# SAVMakerI.net
KiCad netlist of a schematic drawn in EAGLE
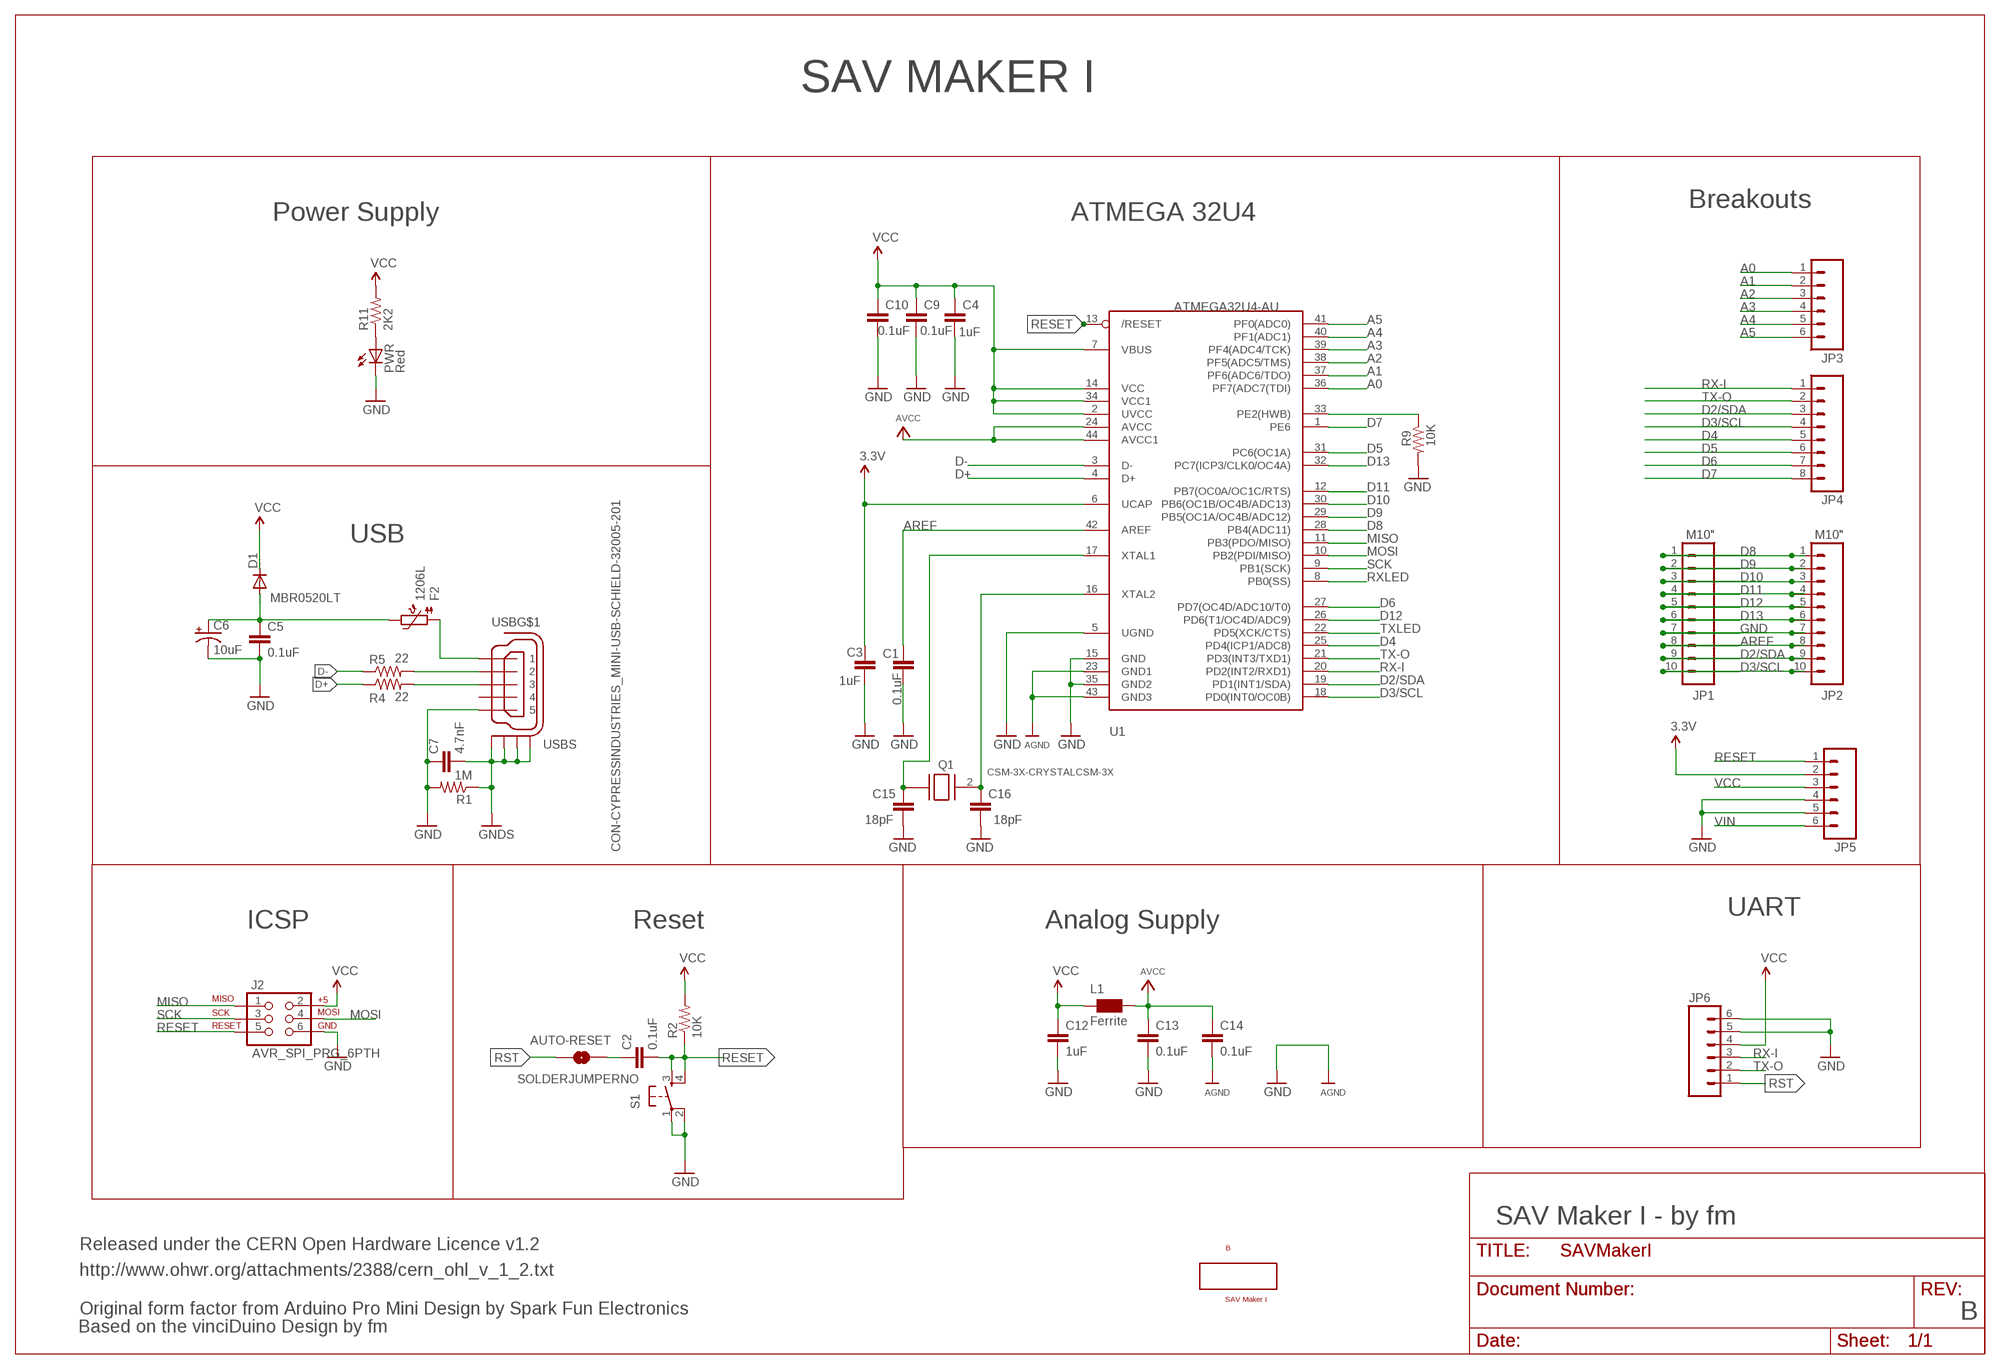
[diagram p0: schematic, sheet 1]

(export (version "E")
  (design (tool "Eeschema 10.0.6"))
  (components
    (comp (ref "AUTO-RESET")
      (value "SOLDERJUMPERNO")
      (footprint "eagle-import:SJ_2S-NO")
      (libsource (lib "eagle-import") (part "SOLDERJUMPERNO"))
    )
    (comp (ref "B")
      (value "SAV Maker I")
      (footprint "eagle-import:BOARD_INFO_BMP")
      (libsource (lib "eagle-import") (part "BOARD_INFO_BMP_20"))
    )
    (comp (ref "C1")
      (value "0.1uF")
      (footprint "eagle-import:1206")
      (libsource (lib "eagle-import") (part "CAP1206"))
    )
    (comp (ref "C2")
      (value "0.1uF")
      (footprint "eagle-import:1206")
      (libsource (lib "eagle-import") (part "CAP1206"))
    )
    (comp (ref "C3")
      (value "1uF")
      (footprint "eagle-import:1206")
      (libsource (lib "eagle-import") (part "CAP1206"))
    )
    (comp (ref "C4")
      (value "1uF")
      (footprint "eagle-import:1206")
      (libsource (lib "eagle-import") (part "CAP1206"))
    )
    (comp (ref "C5")
      (value "0.1uF")
      (footprint "eagle-import:1206")
      (libsource (lib "eagle-import") (part "CAP1206"))
    )
    (comp (ref "C6")
      (value "10uF")
      (footprint "eagle-import:EIA3216")
      (libsource (lib "eagle-import") (part "CAP_POL1206"))
    )
    (comp (ref "C7")
      (value "4.7nF")
      (footprint "eagle-import:1206")
      (libsource (lib "eagle-import") (part "CAP1206"))
    )
    (comp (ref "C9")
      (value "0.1uF")
      (footprint "eagle-import:1206")
      (libsource (lib "eagle-import") (part "CAP1206"))
    )
    (comp (ref "C10")
      (value "0.1uF")
      (footprint "eagle-import:1206")
      (libsource (lib "eagle-import") (part "CAP1206"))
    )
    (comp (ref "C12")
      (value "1uF")
      (footprint "eagle-import:1206")
      (libsource (lib "eagle-import") (part "CAP1206"))
    )
    (comp (ref "C13")
      (value "0.1uF")
      (footprint "eagle-import:1206")
      (libsource (lib "eagle-import") (part "CAP1206"))
    )
    (comp (ref "C14")
      (value "0.1uF")
      (footprint "eagle-import:1206")
      (libsource (lib "eagle-import") (part "CAP1206"))
    )
    (comp (ref "C15")
      (value "18pF")
      (footprint "eagle-import:1206")
      (libsource (lib "eagle-import") (part "CAP1206"))
    )
    (comp (ref "C16")
      (value "18pF")
      (footprint "eagle-import:1206")
      (libsource (lib "eagle-import") (part "CAP1206"))
    )
    (comp (ref "D1")
      (value "MBR0520LT")
      (footprint "eagle-import:SOD123")
      (libsource (lib "eagle-import") (part "MBR0520LT"))
    )
    (comp (ref "F2")
      (value "1206L")
      (footprint "eagle-import:1206_PTC")
      (libsource (lib "eagle-import") (part "PTC1206_L"))
    )
    (comp (ref "J2")
      (value "AVR_SPI_PRG_6PTH")
      (footprint "eagle-import:2X3")
      (libsource (lib "eagle-import") (part "AVR_SPI_PRG_6PTH"))
    )
    (comp (ref "JP1")
      (value "M10\"")
      (footprint "eagle-import:1X10")
      (libsource (lib "eagle-import") (part "M10{dblquote}"))
    )
    (comp (ref "JP2")
      (value "M10\"")
      (footprint "eagle-import:1X10")
      (libsource (lib "eagle-import") (part "M10{dblquote}"))
    )
    (comp (ref "JP3")
      (value "M06SIP")
      (footprint "eagle-import:1X06")
      (libsource (lib "eagle-import") (part "M06SIP"))
    )
    (comp (ref "JP4")
      (value "M081X08")
      (footprint "eagle-import:1X08")
      (libsource (lib "eagle-import") (part "M081X08"))
    )
    (comp (ref "JP5")
      (value "M06SIP")
      (footprint "eagle-import:1X06")
      (libsource (lib "eagle-import") (part "M06SIP"))
    )
    (comp (ref "JP6")
      (value "M06SIP")
      (footprint "eagle-import:1X06")
      (libsource (lib "eagle-import") (part "M06SIP"))
    )
    (comp (ref "L1")
      (value "Ferrite")
      (footprint "eagle-import:1206W")
      (libsource (lib "eagle-import") (part "WE-CBF_1206W"))
    )
    (comp (ref "PWR")
      (value "Red")
      (footprint "eagle-import:LED-1206")
      (libsource (lib "eagle-import") (part "LED1206"))
    )
    (comp (ref "Q1")
      (value "CSM-3X-CRYSTALCSM-3X")
      (footprint "eagle-import:CSM-3X")
      (libsource (lib "eagle-import") (part "CSM-3X-CRYSTALCSM-3X"))
    )
    (comp (ref "R1")
      (value "1M")
      (footprint "eagle-import:R1206")
      (libsource (lib "eagle-import") (part "R-US_R1206"))
    )
    (comp (ref "R2")
      (value "10K")
      (footprint "eagle-import:R1206")
      (libsource (lib "eagle-import") (part "R-US_R1206"))
    )
    (comp (ref "R4")
      (value "22")
      (footprint "eagle-import:R1206")
      (libsource (lib "eagle-import") (part "R-US_R1206"))
    )
    (comp (ref "R5")
      (value "22")
      (footprint "eagle-import:R1206")
      (libsource (lib "eagle-import") (part "R-US_R1206"))
    )
    (comp (ref "R9")
      (value "10K")
      (footprint "eagle-import:R1206")
      (libsource (lib "eagle-import") (part "R-US_R1206"))
    )
    (comp (ref "R11")
      (value "2K2")
      (footprint "eagle-import:R1206")
      (libsource (lib "eagle-import") (part "R-US_R1206"))
    )
    (comp (ref "S1")
      (value "TAC_SWITCHSMD")
      (footprint "eagle-import:TACTILE_SWITCH_SMD")
      (libsource (lib "eagle-import") (part "TAC_SWITCHSMD"))
    )
    (comp (ref "U1")
      (value "ATMEGA32U4-AU")
      (footprint "eagle-import:ADAFRUIT_TQFP44")
      (libsource (lib "eagle-import") (part "ADAFRUIT_ATMEGA32U4-AU"))
    )
    (comp (ref "USB")
      (value "CON-CYPRESSINDUSTRIES_MINI-USB-SCHIELD-32005-201")
      (footprint "eagle-import:CON-CYPRESSINDUSTRIES_32005-201")
      (libsource (lib "eagle-import") (part "CON-CYPRESSINDUSTRIES_MINI-USB-SCHIELD-32005-201"))
    )
  )
  (nets
    (net (code "1") (name "/A0") (class "Default")
      (node (ref "JP3") (pin "1") (pinfunction "1_1") (pintype "passive"))
      (node (ref "U1") (pin "36") (pinfunction "PF7(ADC7(TDI)_36") (pintype "bidirectional"))
    )
    (net (code "2") (name "/A1") (class "Default")
      (node (ref "JP3") (pin "2") (pinfunction "2_2") (pintype "passive"))
      (node (ref "U1") (pin "37") (pinfunction "PF6(ADC6/TDO)_37") (pintype "bidirectional"))
    )
    (net (code "3") (name "/A2") (class "Default")
      (node (ref "JP3") (pin "3") (pinfunction "3_3") (pintype "passive"))
      (node (ref "U1") (pin "38") (pinfunction "PF5(ADC5/TMS)_38") (pintype "bidirectional"))
    )
    (net (code "4") (name "/A3") (class "Default")
      (node (ref "JP3") (pin "4") (pinfunction "4_4") (pintype "passive"))
      (node (ref "U1") (pin "39") (pinfunction "PF4(ADC4/TCK)_39") (pintype "bidirectional"))
    )
    (net (code "5") (name "/A4") (class "Default")
      (node (ref "JP3") (pin "5") (pinfunction "5_5") (pintype "passive"))
      (node (ref "U1") (pin "40") (pinfunction "PF1(ADC1)_40") (pintype "bidirectional"))
    )
    (net (code "6") (name "/A5") (class "Default")
      (node (ref "JP3") (pin "6") (pinfunction "6_6") (pintype "passive"))
      (node (ref "U1") (pin "41") (pinfunction "PF0(ADC0)_41") (pintype "bidirectional"))
    )
    (net (code "7") (name "/AREF") (class "Default")
      (node (ref "C1") (pin "2") (pinfunction "2_2") (pintype "passive"))
      (node (ref "JP1") (pin "8") (pinfunction "8_8") (pintype "passive"))
      (node (ref "JP2") (pin "8") (pinfunction "8_8") (pintype "passive"))
      (node (ref "U1") (pin "42") (pinfunction "AREF_42") (pintype "bidirectional"))
    )
    (net (code "8") (name "/D2{slash}SDA") (class "Default")
      (node (ref "JP1") (pin "9") (pinfunction "9_9") (pintype "passive"))
      (node (ref "JP2") (pin "9") (pinfunction "9_9") (pintype "passive"))
      (node (ref "JP4") (pin "3") (pinfunction "3_3") (pintype "passive"))
      (node (ref "U1") (pin "19") (pinfunction "PD1(INT1/SDA)_19") (pintype "bidirectional"))
    )
    (net (code "9") (name "/D3{slash}SCL") (class "Default")
      (node (ref "JP1") (pin "10") (pinfunction "10_10") (pintype "passive"))
      (node (ref "JP2") (pin "10") (pinfunction "10_10") (pintype "passive"))
      (node (ref "JP4") (pin "4") (pinfunction "4_4") (pintype "passive"))
      (node (ref "U1") (pin "18") (pinfunction "PD0(INT0/OC0B)_18") (pintype "bidirectional"))
    )
    (net (code "10") (name "/D4") (class "Default")
      (node (ref "JP4") (pin "5") (pinfunction "5_5") (pintype "passive"))
      (node (ref "U1") (pin "25") (pinfunction "PD4(ICP1/ADC8)_25") (pintype "bidirectional"))
    )
    (net (code "11") (name "/D5") (class "Default")
      (node (ref "JP4") (pin "6") (pinfunction "6_6") (pintype "passive"))
      (node (ref "U1") (pin "31") (pinfunction "PC6(OC1A)_31") (pintype "bidirectional"))
    )
    (net (code "12") (name "/D6") (class "Default")
      (node (ref "JP4") (pin "7") (pinfunction "7_7") (pintype "passive"))
      (node (ref "U1") (pin "27") (pinfunction "PD7(OC4D/ADC10/T0)_27") (pintype "bidirectional"))
    )
    (net (code "13") (name "/D7") (class "Default")
      (node (ref "JP4") (pin "8") (pinfunction "8_8") (pintype "passive"))
      (node (ref "U1") (pin "1") (pinfunction "PE6_1") (pintype "bidirectional"))
    )
    (net (code "14") (name "/D8") (class "Default")
      (node (ref "JP1") (pin "1") (pinfunction "1_1") (pintype "passive"))
      (node (ref "JP2") (pin "1") (pinfunction "1_1") (pintype "passive"))
      (node (ref "U1") (pin "28") (pinfunction "PB4(ADC11)_28") (pintype "bidirectional"))
    )
    (net (code "15") (name "/D9") (class "Default")
      (node (ref "JP1") (pin "2") (pinfunction "2_2") (pintype "passive"))
      (node (ref "JP2") (pin "2") (pinfunction "2_2") (pintype "passive"))
      (node (ref "U1") (pin "29") (pinfunction "PB5(OC1A/OC4B/ADC12)_29") (pintype "bidirectional"))
    )
    (net (code "16") (name "/D10") (class "Default")
      (node (ref "JP1") (pin "3") (pinfunction "3_3") (pintype "passive"))
      (node (ref "JP2") (pin "3") (pinfunction "3_3") (pintype "passive"))
      (node (ref "U1") (pin "30") (pinfunction "PB6(OC1B/OC4B/ADC13)_30") (pintype "bidirectional"))
    )
    (net (code "17") (name "/D11") (class "Default")
      (node (ref "JP1") (pin "4") (pinfunction "4_4") (pintype "passive"))
      (node (ref "JP2") (pin "4") (pinfunction "4_4") (pintype "passive"))
      (node (ref "U1") (pin "12") (pinfunction "PB7(OC0A/OC1C/RTS)_12") (pintype "bidirectional"))
    )
    (net (code "18") (name "/D12") (class "Default")
      (node (ref "JP1") (pin "5") (pinfunction "5_5") (pintype "passive"))
      (node (ref "JP2") (pin "5") (pinfunction "5_5") (pintype "passive"))
      (node (ref "U1") (pin "26") (pinfunction "PD6(T1/OC4D/ADC9)_26") (pintype "bidirectional"))
    )
    (net (code "19") (name "/D13") (class "Default")
      (node (ref "JP1") (pin "6") (pinfunction "6_6") (pintype "passive"))
      (node (ref "JP2") (pin "6") (pinfunction "6_6") (pintype "passive"))
      (node (ref "U1") (pin "32") (pinfunction "PC7(ICP3/CLK0/OC4A)_32") (pintype "bidirectional"))
    )
    (net (code "20") (name "/MISO") (class "Default")
      (node (ref "J2") (pin "1") (pinfunction "1_1") (pintype "passive"))
      (node (ref "U1") (pin "11") (pinfunction "PB3(PDO/MISO)_11") (pintype "bidirectional"))
    )
    (net (code "21") (name "/MOSI") (class "Default")
      (node (ref "J2") (pin "4") (pinfunction "4_4") (pintype "passive"))
      (node (ref "U1") (pin "10") (pinfunction "PB2(PDI/MISO)_10") (pintype "bidirectional"))
    )
    (net (code "22") (name "/RX-I") (class "Default")
      (node (ref "JP4") (pin "1") (pinfunction "1_1") (pintype "passive"))
      (node (ref "JP6") (pin "3") (pinfunction "3_3") (pintype "passive"))
      (node (ref "U1") (pin "20") (pinfunction "PD2(INT2/RXD1)_20") (pintype "bidirectional"))
    )
    (net (code "23") (name "/RXLED") (class "Default")
      (node (ref "U1") (pin "8") (pinfunction "PB0(SS)_8") (pintype "bidirectional"))
    )
    (net (code "24") (name "/SCK") (class "Default")
      (node (ref "J2") (pin "3") (pinfunction "3_3") (pintype "passive"))
      (node (ref "U1") (pin "9") (pinfunction "PB1(SCK)_9") (pintype "bidirectional"))
    )
    (net (code "25") (name "/TX-O") (class "Default")
      (node (ref "JP4") (pin "2") (pinfunction "2_2") (pintype "passive"))
      (node (ref "JP6") (pin "2") (pinfunction "2_2") (pintype "passive"))
      (node (ref "U1") (pin "21") (pinfunction "PD3(INT3/TXD1)_21") (pintype "bidirectional"))
    )
    (net (code "26") (name "/TXLED") (class "Default")
      (node (ref "U1") (pin "22") (pinfunction "PD5(XCK/CTS)_22") (pintype "bidirectional"))
    )
    (net (code "27") (name "/VIN") (class "Default")
      (node (ref "JP5") (pin "6") (pinfunction "6_6") (pintype "passive"))
    )
    (net (code "28") (name "3.3V") (class "Default")
      (node (ref "C3") (pin "1") (pinfunction "1_1") (pintype "passive"))
      (node (ref "JP5") (pin "2") (pinfunction "2_2") (pintype "passive"))
      (node (ref "U1") (pin "6") (pinfunction "UCAP_6") (pintype "bidirectional"))
    )
    (net (code "29") (name "AGND") (class "Default")
      (node (ref "C1") (pin "1") (pinfunction "1_1") (pintype "passive"))
      (node (ref "C10") (pin "2") (pinfunction "2_2") (pintype "passive"))
      (node (ref "C12") (pin "2") (pinfunction "2_2") (pintype "passive"))
      (node (ref "C13") (pin "2") (pinfunction "2_2") (pintype "passive"))
      (node (ref "C14") (pin "2") (pinfunction "2_2") (pintype "passive"))
      (node (ref "C15") (pin "2") (pinfunction "2_2") (pintype "passive"))
      (node (ref "C16") (pin "2") (pinfunction "2_2") (pintype "passive"))
      (node (ref "C3") (pin "2") (pinfunction "2_2") (pintype "passive"))
      (node (ref "C4") (pin "2") (pinfunction "2_2") (pintype "passive"))
      (node (ref "C5") (pin "2") (pinfunction "2_2") (pintype "passive"))
      (node (ref "C6") (pin "C") (pinfunction "-_C") (pintype "passive"))
      (node (ref "C7") (pin "1") (pinfunction "1_1") (pintype "passive"))
      (node (ref "C9") (pin "2") (pinfunction "2_2") (pintype "passive"))
      (node (ref "J2") (pin "6") (pinfunction "6_6") (pintype "passive"))
      (node (ref "JP1") (pin "7") (pinfunction "7_7") (pintype "passive"))
      (node (ref "JP2") (pin "7") (pinfunction "7_7") (pintype "passive"))
      (node (ref "JP5") (pin "4") (pinfunction "4_4") (pintype "passive"))
      (node (ref "JP5") (pin "5") (pinfunction "5_5") (pintype "passive"))
      (node (ref "JP6") (pin "5") (pinfunction "5_5") (pintype "passive"))
      (node (ref "JP6") (pin "6") (pinfunction "6_6") (pintype "passive"))
      (node (ref "PWR") (pin "C") (pinfunction "C_C") (pintype "passive"))
      (node (ref "R1") (pin "2") (pinfunction "2_2") (pintype "passive"))
      (node (ref "R9") (pin "2") (pinfunction "2_2") (pintype "passive"))
      (node (ref "S1") (pin "1") (pinfunction "1_1") (pintype "passive"))
      (node (ref "S1") (pin "2") (pinfunction "2_2") (pintype "passive"))
      (node (ref "U1") (pin "15") (pinfunction "GND_15") (pintype "bidirectional"))
      (node (ref "U1") (pin "23") (pinfunction "GND1_23") (pintype "bidirectional"))
      (node (ref "U1") (pin "35") (pinfunction "GND2_35") (pintype "bidirectional"))
      (node (ref "U1") (pin "43") (pinfunction "GND3_43") (pintype "bidirectional"))
      (node (ref "U1") (pin "5") (pinfunction "UGND_5") (pintype "bidirectional"))
      (node (ref "USB") (pin "5") (pinfunction "5_5") (pintype "passive"))
    )
    (net (code "30") (name "AVCC") (class "Default")
      (node (ref "C13") (pin "1") (pinfunction "1_1") (pintype "passive"))
      (node (ref "C14") (pin "1") (pinfunction "1_1") (pintype "passive"))
      (node (ref "L1") (pin "2") (pinfunction "2_2") (pintype "passive"))
      (node (ref "U1") (pin "24") (pinfunction "AVCC_24") (pintype "bidirectional"))
      (node (ref "U1") (pin "44") (pinfunction "AVCC1_44") (pintype "bidirectional"))
    )
    (net (code "31") (name "D+") (class "Default")
      (node (ref "R4") (pin "1") (pinfunction "1_1") (pintype "passive"))
      (node (ref "U1") (pin "4") (pinfunction "D+_4") (pintype "bidirectional"))
    )
    (net (code "32") (name "D-") (class "Default")
      (node (ref "R5") (pin "1") (pinfunction "1_1") (pintype "passive"))
      (node (ref "U1") (pin "3") (pinfunction "D-_3") (pintype "bidirectional"))
    )
    (net (code "33") (name "GNDS") (class "Default")
      (node (ref "C7") (pin "2") (pinfunction "2_2") (pintype "passive"))
      (node (ref "R1") (pin "1") (pinfunction "1_1") (pintype "passive"))
      (node (ref "USB") (pin "M1") (pinfunction "S1_M1") (pintype "passive"))
      (node (ref "USB") (pin "M2") (pinfunction "S2_M2") (pintype "passive"))
      (node (ref "USB") (pin "M3") (pinfunction "S3_M3") (pintype "passive"))
      (node (ref "USB") (pin "M4") (pinfunction "S4_M4") (pintype "passive"))
    )
    (net (code "34") (name "Net-(AUTO-RESET-Pad2)") (class "Default")
      (node (ref "AUTO-RESET") (pin "2") (pinfunction "2_2") (pintype "passive"))
      (node (ref "C2") (pin "1") (pinfunction "1_1") (pintype "passive"))
    )
    (net (code "35") (name "Net-(C6-+)") (class "Default")
      (node (ref "C5") (pin "1") (pinfunction "1_1") (pintype "passive"))
      (node (ref "C6") (pin "A") (pinfunction "+_A") (pintype "passive"))
      (node (ref "D1") (pin "A") (pinfunction "A_A") (pintype "passive"))
      (node (ref "F2") (pin "2") (pinfunction "2_2") (pintype "passive"))
    )
    (net (code "36") (name "Net-(F2-Pad1)") (class "Default")
      (node (ref "F2") (pin "1") (pinfunction "1_1") (pintype "passive"))
      (node (ref "USB") (pin "1") (pinfunction "1_1") (pintype "passive"))
    )
    (net (code "37") (name "Net-(PWR-PadA)") (class "Default")
      (node (ref "PWR") (pin "A") (pinfunction "A_A") (pintype "passive"))
      (node (ref "R11") (pin "1") (pinfunction "1_1") (pintype "passive"))
    )
    (net (code "38") (name "Net-(R4-Pad2)") (class "Default")
      (node (ref "R4") (pin "2") (pinfunction "2_2") (pintype "passive"))
      (node (ref "USB") (pin "3") (pinfunction "3_3") (pintype "passive"))
    )
    (net (code "39") (name "Net-(R5-Pad2)") (class "Default")
      (node (ref "R5") (pin "2") (pinfunction "2_2") (pintype "passive"))
      (node (ref "USB") (pin "2") (pinfunction "2_2") (pintype "passive"))
    )
    (net (code "40") (name "Net-(U1-PE2(HWB))") (class "Default")
      (node (ref "R9") (pin "1") (pinfunction "1_1") (pintype "passive"))
      (node (ref "U1") (pin "33") (pinfunction "PE2(HWB)_33") (pintype "bidirectional"))
    )
    (net (code "41") (name "Net-(U1-XTAL1)") (class "Default")
      (node (ref "C15") (pin "1") (pinfunction "1_1") (pintype "passive"))
      (node (ref "Q1") (pin "1") (pinfunction "1_1") (pintype "bidirectional"))
      (node (ref "U1") (pin "17") (pinfunction "XTAL1_17") (pintype "bidirectional"))
    )
    (net (code "42") (name "Net-(U1-XTAL2)") (class "Default")
      (node (ref "C16") (pin "1") (pinfunction "1_1") (pintype "passive"))
      (node (ref "Q1") (pin "2") (pinfunction "2_2") (pintype "bidirectional"))
      (node (ref "U1") (pin "16") (pinfunction "XTAL2_16") (pintype "bidirectional"))
    )
    (net (code "43") (name "RESET") (class "Default")
      (node (ref "C2") (pin "2") (pinfunction "2_2") (pintype "passive"))
      (node (ref "J2") (pin "5") (pinfunction "5_5") (pintype "passive"))
      (node (ref "JP5") (pin "1") (pinfunction "1_1") (pintype "passive"))
      (node (ref "R2") (pin "1") (pinfunction "1_1") (pintype "passive"))
      (node (ref "S1") (pin "3") (pinfunction "3_3") (pintype "passive"))
      (node (ref "S1") (pin "4") (pinfunction "4_4") (pintype "passive"))
      (node (ref "U1") (pin "13") (pinfunction "/RESET_13") (pintype "bidirectional"))
    )
    (net (code "44") (name "RST") (class "Default")
      (node (ref "AUTO-RESET") (pin "1") (pinfunction "1_1") (pintype "passive"))
      (node (ref "JP6") (pin "1") (pinfunction "1_1") (pintype "passive"))
    )
    (net (code "45") (name "VCC") (class "Default")
      (node (ref "C10") (pin "1") (pinfunction "1_1") (pintype "passive"))
      (node (ref "C12") (pin "1") (pinfunction "1_1") (pintype "passive"))
      (node (ref "C4") (pin "1") (pinfunction "1_1") (pintype "passive"))
      (node (ref "C9") (pin "1") (pinfunction "1_1") (pintype "passive"))
      (node (ref "D1") (pin "C") (pinfunction "C_C") (pintype "passive"))
      (node (ref "J2") (pin "2") (pinfunction "2_2") (pintype "passive"))
      (node (ref "JP5") (pin "3") (pinfunction "3_3") (pintype "passive"))
      (node (ref "JP6") (pin "4") (pinfunction "4_4") (pintype "passive"))
      (node (ref "L1") (pin "1") (pinfunction "1_1") (pintype "passive"))
      (node (ref "R11") (pin "2") (pinfunction "2_2") (pintype "passive"))
      (node (ref "R2") (pin "2") (pinfunction "2_2") (pintype "passive"))
      (node (ref "U1") (pin "14") (pinfunction "VCC_14") (pintype "bidirectional"))
      (node (ref "U1") (pin "2") (pinfunction "UVCC_2") (pintype "bidirectional"))
      (node (ref "U1") (pin "34") (pinfunction "VCC1_34") (pintype "bidirectional"))
      (node (ref "U1") (pin "7") (pinfunction "VBUS_7") (pintype "bidirectional"))
    )
    (net (code "46") (name "unconnected-(USB-Pad4)") (class "Default")
      (node (ref "USB") (pin "4") (pinfunction "4_4") (pintype "passive"))
    )
  )
)
